# Sheet1.net
KiCad netlist of a schematic drawn in Altium Designer
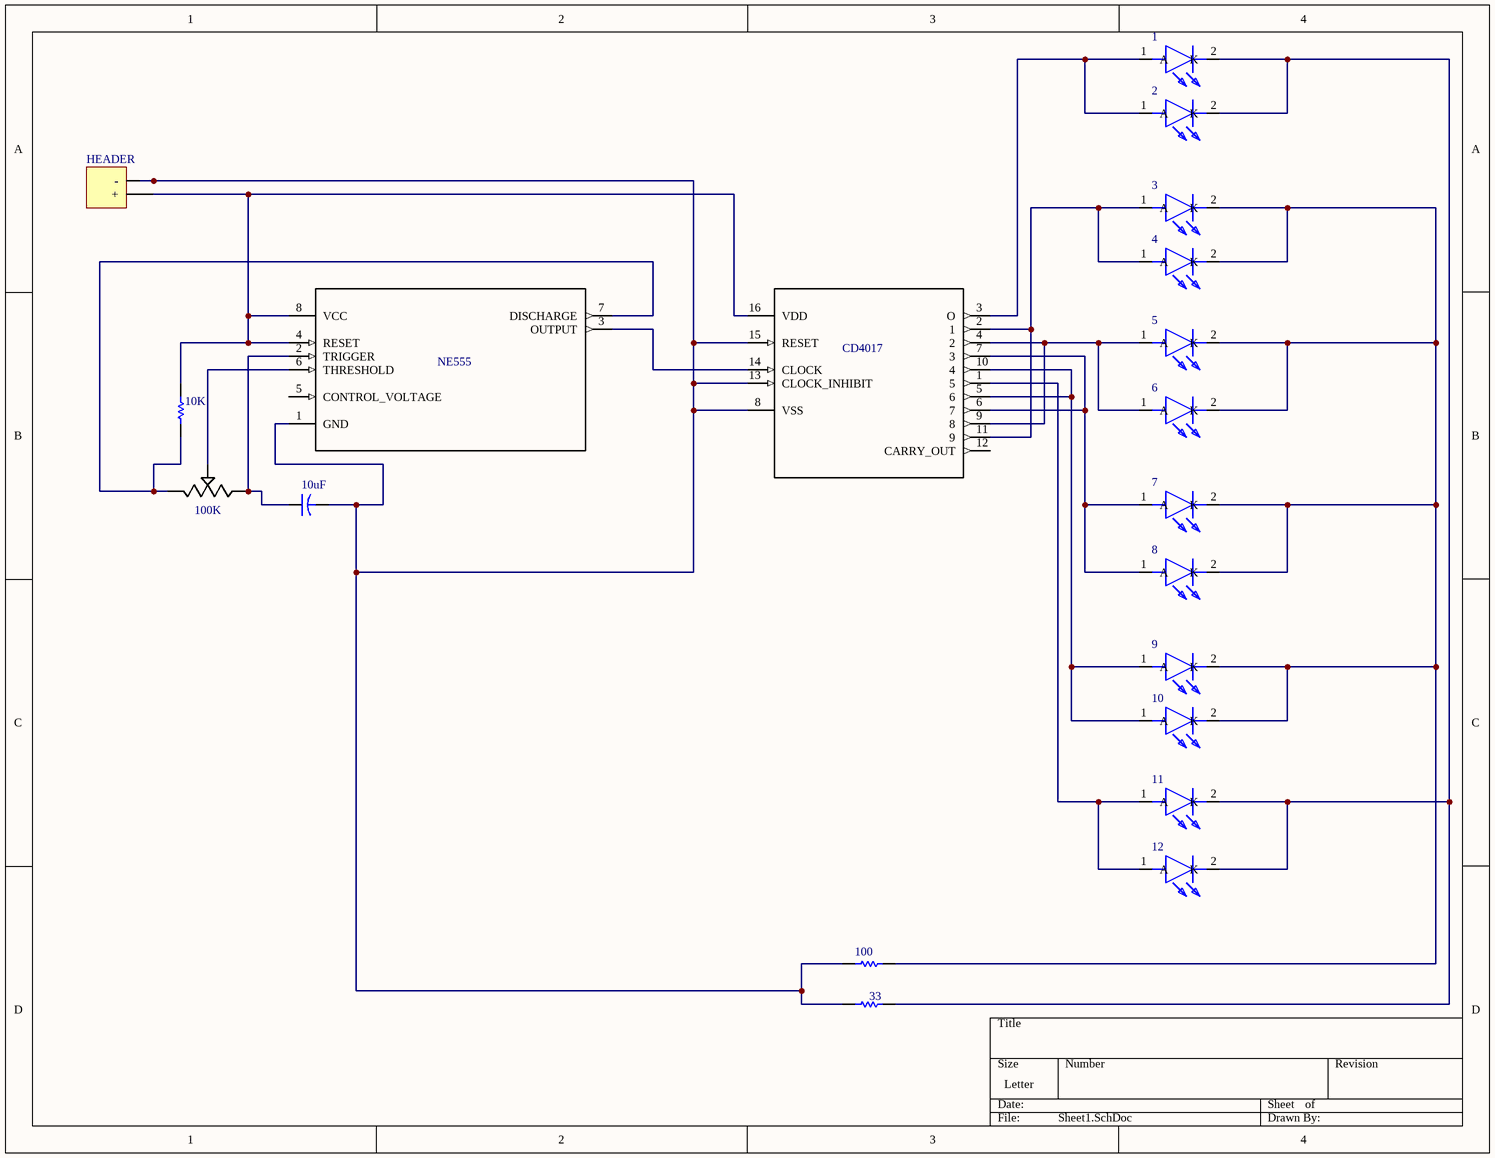
[diagram p0: Sheet1.SchDoc]

(export (version "E")
  (design (tool "Eeschema 10.0.6"))
  (components
    (comp (ref "1")
      (value "L-53GD")
      (footprint "SamacSys:L-53GD")
      (description "LED")
      (fields (field (name "RS PART NUMBER") "2286004A"))
      (libsource (lib "SamacSys") (part "L-53GD"))
    )
    (comp (ref "2")
      (value "L-53GD")
      (footprint "SamacSys:L-53GD")
      (description "LED")
      (fields (field (name "RS PART NUMBER") "2286004A"))
      (libsource (lib "SamacSys") (part "L-53GD"))
    )
    (comp (ref "3")
      (value "L-53GD")
      (footprint "SamacSys:L-53GD")
      (description "LED")
      (fields (field (name "RS PART NUMBER") "2286004A"))
      (libsource (lib "SamacSys") (part "L-53GD"))
    )
    (comp (ref "4")
      (value "L-53GD")
      (footprint "SamacSys:L-53GD")
      (description "LED")
      (fields (field (name "RS PART NUMBER") "2286004A"))
      (libsource (lib "SamacSys") (part "L-53GD"))
    )
    (comp (ref "5")
      (value "L-53GD")
      (footprint "SamacSys:L-53GD")
      (description "LED")
      (fields (field (name "RS PART NUMBER") "2286004A"))
      (libsource (lib "SamacSys") (part "L-53GD"))
    )
    (comp (ref "6")
      (value "L-53GD")
      (footprint "SamacSys:L-53GD")
      (description "LED")
      (fields (field (name "RS PART NUMBER") "2286004A"))
      (libsource (lib "SamacSys") (part "L-53GD"))
    )
    (comp (ref "7")
      (value "L-53GD")
      (footprint "SamacSys:L-53GD")
      (description "LED")
      (fields (field (name "RS PART NUMBER") "2286004A"))
      (libsource (lib "SamacSys") (part "L-53GD"))
    )
    (comp (ref "8")
      (value "L-53GD")
      (footprint "SamacSys:L-53GD")
      (description "LED")
      (fields (field (name "RS PART NUMBER") "2286004A"))
      (libsource (lib "SamacSys") (part "L-53GD"))
    )
    (comp (ref "9")
      (value "L-53GD")
      (footprint "SamacSys:L-53GD")
      (description "LED")
      (fields (field (name "RS PART NUMBER") "2286004A"))
      (libsource (lib "SamacSys") (part "L-53GD"))
    )
    (comp (ref "10")
      (value "L-53GD")
      (footprint "SamacSys:L-53GD")
      (description "LED")
      (fields (field (name "RS PART NUMBER") "2286004A"))
      (libsource (lib "SamacSys") (part "L-53GD"))
    )
    (comp (ref "10K")
      (value "Res1")
      (footprint "AXIAL-0.3")
      (description "Resistor")
      (fields (field (name "PUBLISHER") "Altium Limited"))
      (libsource (lib "Miscellaneous Devices") (part "Res1"))
    )
    (comp (ref "10uF")
      (value "Cap2")
      (footprint "CAPR5-4X5")
      (description "Capacitor")
      (fields (field (name "PUBLISHER") "Altium Limited"))
      (libsource (lib "Miscellaneous Devices") (part "Cap2"))
    )
    (comp (ref "11")
      (value "L-53GD")
      (footprint "SamacSys:L-53GD")
      (description "LED")
      (fields (field (name "RS PART NUMBER") "2286004A"))
      (libsource (lib "SamacSys") (part "L-53GD"))
    )
    (comp (ref "12")
      (value "L-53GD")
      (footprint "SamacSys:L-53GD")
      (description "LED")
      (fields (field (name "RS PART NUMBER") "2286004A"))
      (libsource (lib "SamacSys") (part "L-53GD"))
    )
    (comp (ref "33")
      (value "Res1")
      (footprint "AXIAL-0.3")
      (description "Resistor")
      (fields (field (name "PUBLISHER") "Altium Limited"))
      (libsource (lib "Miscellaneous Devices") (part "Res1"))
    )
    (comp (ref "100")
      (value "Res1")
      (footprint "AXIAL-0.3")
      (description "Resistor")
      (fields (field (name "PUBLISHER") "Altium Limited"))
      (libsource (lib "Miscellaneous Devices") (part "Res1"))
    )
    (comp (ref "100K")
      (value "EVN-D8AA03B14")
      (footprint "*TRIM_EVN-D8AA03B14")
      (description "Trimmer; Carbon; Rest 10 Kilohms; PCB; 1 Turn; Pwr-Rtg 0.1 W; Linear; Top Adj; 6 mm SQ")
      (fields (field (name "MF") "Panasonic Electronic"))
      (libsource (lib "EVN-D8AA03B14") (part "EVN-D8AA03B14"))
    )
    (comp (ref "CD4017")
      (value "CD4017BE")
      (footprint "*DIP254P762X508-16")
      (description "IC Mos 4017/CD4017BE HARRIS")
      (fields (field (name "MF") "Texas"))
      (libsource (lib "CD4017BE") (part "CD4017BE"))
    )
    (comp (ref "HEADER")
      (value "Header 2")
      (footprint "HDR1X2")
      (description "Header, 2-Pin")
      (fields (field (name "PUBLISHER") "Altium Limited"))
      (libsource (lib "Miscellaneous Connectors") (part "Header 2"))
    )
    (comp (ref "NE555")
      (value "NE555N")
      (footprint "*DIP254P762X533-8")
      (fields (field (name "MF") "ON Semiconductor"))
      (libsource (lib "NE555N") (part "NE555N"))
    )
  )
  (nets
    (net (code "1") (name "Net-(1-A)") (class "Default")
      (node (ref "1") (pin "1") (pinfunction "A_1") (pintype "passive"))
      (node (ref "2") (pin "1") (pinfunction "A_1") (pintype "passive"))
      (node (ref "CD4017") (pin "3") (pinfunction "O_3") (pintype "output"))
    )
    (net (code "2") (name "Net-(1-K)") (class "Default")
      (node (ref "1") (pin "2") (pinfunction "K_2") (pintype "passive"))
      (node (ref "11") (pin "2") (pinfunction "K_2") (pintype "passive"))
      (node (ref "12") (pin "2") (pinfunction "K_2") (pintype "passive"))
      (node (ref "2") (pin "2") (pinfunction "K_2") (pintype "passive"))
      (node (ref "33") (pin "2") (pinfunction "2_2") (pintype "passive"))
    )
    (net (code "3") (name "Net-(3-A)") (class "Default")
      (node (ref "3") (pin "1") (pinfunction "A_1") (pintype "passive"))
      (node (ref "4") (pin "1") (pinfunction "A_1") (pintype "passive"))
      (node (ref "CD4017") (pin "11") (pinfunction "9_11") (pintype "output"))
      (node (ref "CD4017") (pin "2") (pinfunction "1_2") (pintype "output"))
    )
    (net (code "4") (name "Net-(5-A)") (class "Default")
      (node (ref "5") (pin "1") (pinfunction "A_1") (pintype "passive"))
      (node (ref "6") (pin "1") (pinfunction "A_1") (pintype "passive"))
      (node (ref "CD4017") (pin "4") (pinfunction "2_4") (pintype "output"))
      (node (ref "CD4017") (pin "9") (pinfunction "8_9") (pintype "output"))
    )
    (net (code "5") (name "Net-(7-A)") (class "Default")
      (node (ref "7") (pin "1") (pinfunction "A_1") (pintype "passive"))
      (node (ref "8") (pin "1") (pinfunction "A_1") (pintype "passive"))
      (node (ref "CD4017") (pin "6") (pinfunction "7_6") (pintype "output"))
      (node (ref "CD4017") (pin "7") (pinfunction "3_7") (pintype "output"))
    )
    (net (code "6") (name "Net-(10-A)") (class "Default")
      (node (ref "10") (pin "1") (pinfunction "A_1") (pintype "passive"))
      (node (ref "9") (pin "1") (pinfunction "A_1") (pintype "passive"))
      (node (ref "CD4017") (pin "10") (pinfunction "4_10") (pintype "output"))
      (node (ref "CD4017") (pin "5") (pinfunction "6_5") (pintype "output"))
    )
    (net (code "7") (name "Net-(10-K)") (class "Default")
      (node (ref "10") (pin "2") (pinfunction "K_2") (pintype "passive"))
      (node (ref "100") (pin "2") (pinfunction "2_2") (pintype "passive"))
      (node (ref "3") (pin "2") (pinfunction "K_2") (pintype "passive"))
      (node (ref "4") (pin "2") (pinfunction "K_2") (pintype "passive"))
      (node (ref "5") (pin "2") (pinfunction "K_2") (pintype "passive"))
      (node (ref "6") (pin "2") (pinfunction "K_2") (pintype "passive"))
      (node (ref "7") (pin "2") (pinfunction "K_2") (pintype "passive"))
      (node (ref "8") (pin "2") (pinfunction "K_2") (pintype "passive"))
      (node (ref "9") (pin "2") (pinfunction "K_2") (pintype "passive"))
    )
    (net (code "8") (name "Net-(11-A)") (class "Default")
      (node (ref "11") (pin "1") (pinfunction "A_1") (pintype "passive"))
      (node (ref "12") (pin "1") (pinfunction "A_1") (pintype "passive"))
      (node (ref "CD4017") (pin "1") (pinfunction "5_1") (pintype "output"))
    )
    (net (code "9") (name "Net-(CD4017-CLOCK)") (class "Default")
      (node (ref "CD4017") (pin "14") (pinfunction "CLOCK_14") (pintype "input"))
      (node (ref "NE555") (pin "3") (pinfunction "OUTPUT_3") (pintype "output"))
    )
    (net (code "10") (name "Net-(CD4017-CLOCK_INHIBIT)") (class "Default")
      (node (ref "100") (pin "1") (pinfunction "1_1") (pintype "passive"))
      (node (ref "10uF") (pin "2") (pinfunction "2_2") (pintype "passive"))
      (node (ref "33") (pin "1") (pinfunction "1_1") (pintype "passive"))
      (node (ref "CD4017") (pin "13") (pinfunction "CLOCK_INHIBIT_13") (pintype "input"))
      (node (ref "CD4017") (pin "15") (pinfunction "RESET_15") (pintype "input"))
      (node (ref "CD4017") (pin "8") (pinfunction "VSS_8") (pintype "power_in"))
      (node (ref "HEADER") (pin "2") (pinfunction "-_2") (pintype "passive"))
      (node (ref "NE555") (pin "1") (pinfunction "GND_1") (pintype "passive"))
    )
    (net (code "11") (name "Net-(CD4017-VDD)") (class "Default")
      (node (ref "10K") (pin "2") (pinfunction "2_2") (pintype "passive"))
      (node (ref "CD4017") (pin "16") (pinfunction "VDD_16") (pintype "power_in"))
      (node (ref "HEADER") (pin "1") (pinfunction "+_1") (pintype "passive"))
      (node (ref "NE555") (pin "4") (pinfunction "RESET_4") (pintype "input"))
      (node (ref "NE555") (pin "8") (pinfunction "VCC_8") (pintype "power_in"))
    )
    (net (code "12") (name "Net-(NE555-DISCHARGE)") (class "Default")
      (node (ref "100K") (pin "3") (pinfunction "3_3") (pintype "passive"))
      (node (ref "10K") (pin "1") (pinfunction "1_1") (pintype "passive"))
      (node (ref "NE555") (pin "7") (pinfunction "DISCHARGE_7") (pintype "output"))
    )
    (net (code "13") (name "Net-(NE555-THRESHOLD)") (class "Default")
      (node (ref "100K") (pin "2") (pinfunction "2_2") (pintype "passive"))
      (node (ref "NE555") (pin "6") (pinfunction "THRESHOLD_6") (pintype "input"))
    )
    (net (code "14") (name "Net-(NE555-TRIGGER)") (class "Default")
      (node (ref "100K") (pin "1") (pinfunction "1_1") (pintype "passive"))
      (node (ref "10uF") (pin "1") (pinfunction "1_1") (pintype "passive"))
      (node (ref "NE555") (pin "2") (pinfunction "TRIGGER_2") (pintype "input"))
    )
    (net (code "15") (name "unconnected-(CD4017-CARRY_OUT-Pad12)") (class "Default")
      (node (ref "CD4017") (pin "12") (pinfunction "CARRY_OUT_12") (pintype "output"))
    )
    (net (code "16") (name "unconnected-(NE555-CONTROL_VOLTAGE-Pad5)") (class "Default")
      (node (ref "NE555") (pin "5") (pinfunction "CONTROL_VOLTAGE_5") (pintype "input"))
    )
  )
)
